# tbs4.net
KiCad netlist of a schematic drawn in EAGLE
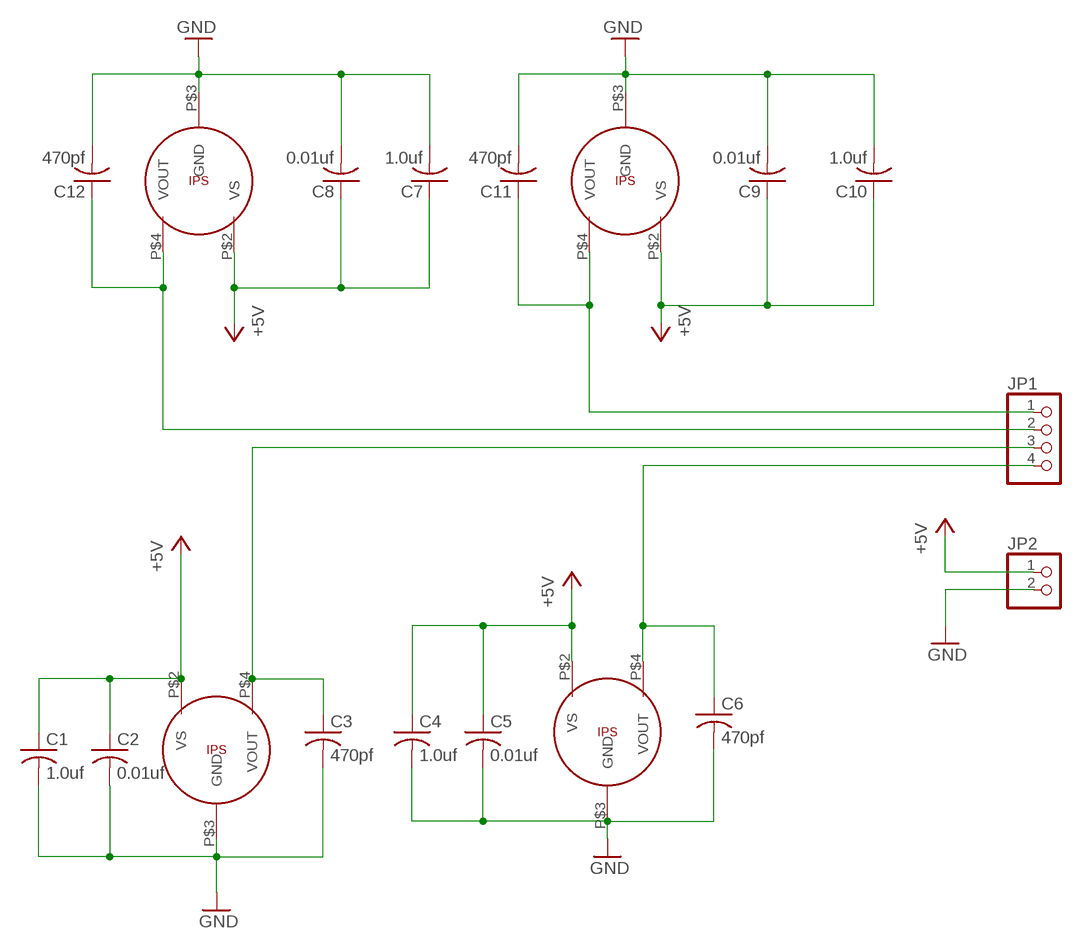
[diagram p0: schematic, sheet 1]

(export (version "E")
  (design (tool "Eeschema 10.0.6"))
  (components
    (comp (ref "C1")
      (value "1.0uf")
      (footprint "eagle-import:C0603")
      (libsource (lib "eagle-import") (part "C-USC0603"))
    )
    (comp (ref "C2")
      (value "0.01uf")
      (footprint "eagle-import:C0603")
      (libsource (lib "eagle-import") (part "C-USC0603"))
    )
    (comp (ref "C3")
      (value "470pf")
      (footprint "eagle-import:C0603")
      (libsource (lib "eagle-import") (part "C-USC0603"))
    )
    (comp (ref "C4")
      (value "1.0uf")
      (footprint "eagle-import:C0603")
      (libsource (lib "eagle-import") (part "C-USC0603"))
    )
    (comp (ref "C5")
      (value "0.01uf")
      (footprint "eagle-import:C0603")
      (libsource (lib "eagle-import") (part "C-USC0603"))
    )
    (comp (ref "C6")
      (value "470pf")
      (footprint "eagle-import:C0603")
      (libsource (lib "eagle-import") (part "C-USC0603"))
    )
    (comp (ref "C7")
      (value "1.0uf")
      (footprint "eagle-import:C0603")
      (libsource (lib "eagle-import") (part "C-USC0603"))
    )
    (comp (ref "C8")
      (value "0.01uf")
      (footprint "eagle-import:C0603")
      (libsource (lib "eagle-import") (part "C-USC0603"))
    )
    (comp (ref "C9")
      (value "0.01uf")
      (footprint "eagle-import:C0603")
      (libsource (lib "eagle-import") (part "C-USC0603"))
    )
    (comp (ref "C10")
      (value "1.0uf")
      (footprint "eagle-import:C0603")
      (libsource (lib "eagle-import") (part "C-USC0603"))
    )
    (comp (ref "C11")
      (value "470pf")
      (footprint "eagle-import:C0603")
      (libsource (lib "eagle-import") (part "C-USC0603"))
    )
    (comp (ref "C12")
      (value "470pf")
      (footprint "eagle-import:C0603")
      (libsource (lib "eagle-import") (part "C-USC0603"))
    )
    (comp (ref "IPS1")
      (value "MPXV5050VC6T1")
      (footprint "eagle-import:SOP-CASE-482A")
      (libsource (lib "eagle-import") (part "MPXV5050VC6T1"))
    )
    (comp (ref "IPS2")
      (value "MPXV5050VC6T1")
      (footprint "eagle-import:SOP-CASE-482A")
      (libsource (lib "eagle-import") (part "MPXV5050VC6T1"))
    )
    (comp (ref "IPS3")
      (value "MPXV5050VC6T1")
      (footprint "eagle-import:SOP-CASE-482A")
      (libsource (lib "eagle-import") (part "MPXV5050VC6T1"))
    )
    (comp (ref "IPS4")
      (value "MPXV5050VC6T1")
      (footprint "eagle-import:SOP-CASE-482A")
      (libsource (lib "eagle-import") (part "MPXV5050VC6T1"))
    )
    (comp (ref "JP1")
      (value "PINHD-1X4")
      (footprint "eagle-import:1X04")
      (libsource (lib "eagle-import") (part "PINHD-1X4"))
    )
    (comp (ref "JP2")
      (value "PINHD-1X2")
      (footprint "eagle-import:1X02")
      (libsource (lib "eagle-import") (part "PINHD-1X2"))
    )
  )
  (nets
    (net (code "1") (name "+5V") (class "Default")
      (node (ref "C1") (pin "1") (pinfunction "1_1") (pintype "passive"))
      (node (ref "C10") (pin "1") (pinfunction "1_1") (pintype "passive"))
      (node (ref "C2") (pin "1") (pinfunction "1_1") (pintype "passive"))
      (node (ref "C4") (pin "1") (pinfunction "1_1") (pintype "passive"))
      (node (ref "C5") (pin "1") (pinfunction "1_1") (pintype "passive"))
      (node (ref "C7") (pin "1") (pinfunction "1_1") (pintype "passive"))
      (node (ref "C8") (pin "1") (pinfunction "1_1") (pintype "passive"))
      (node (ref "C9") (pin "1") (pinfunction "1_1") (pintype "passive"))
      (node (ref "IPS1") (pin "P$2") (pinfunction "VS_P$2") (pintype "power_in"))
      (node (ref "IPS2") (pin "P$2") (pinfunction "VS_P$2") (pintype "power_in"))
      (node (ref "IPS3") (pin "P$2") (pinfunction "VS_P$2") (pintype "power_in"))
      (node (ref "IPS4") (pin "P$2") (pinfunction "VS_P$2") (pintype "power_in"))
      (node (ref "JP2") (pin "1") (pinfunction "1_1") (pintype "passive"))
    )
    (net (code "2") (name "GND") (class "Default")
      (node (ref "C1") (pin "2") (pinfunction "2_2") (pintype "passive"))
      (node (ref "C10") (pin "2") (pinfunction "2_2") (pintype "passive"))
      (node (ref "C11") (pin "2") (pinfunction "2_2") (pintype "passive"))
      (node (ref "C12") (pin "2") (pinfunction "2_2") (pintype "passive"))
      (node (ref "C2") (pin "2") (pinfunction "2_2") (pintype "passive"))
      (node (ref "C3") (pin "2") (pinfunction "2_2") (pintype "passive"))
      (node (ref "C4") (pin "2") (pinfunction "2_2") (pintype "passive"))
      (node (ref "C5") (pin "2") (pinfunction "2_2") (pintype "passive"))
      (node (ref "C6") (pin "2") (pinfunction "2_2") (pintype "passive"))
      (node (ref "C7") (pin "2") (pinfunction "2_2") (pintype "passive"))
      (node (ref "C8") (pin "2") (pinfunction "2_2") (pintype "passive"))
      (node (ref "C9") (pin "2") (pinfunction "2_2") (pintype "passive"))
      (node (ref "IPS1") (pin "P$3") (pinfunction "GND_P$3") (pintype "power_in"))
      (node (ref "IPS2") (pin "P$3") (pinfunction "GND_P$3") (pintype "power_in"))
      (node (ref "IPS3") (pin "P$3") (pinfunction "GND_P$3") (pintype "power_in"))
      (node (ref "IPS4") (pin "P$3") (pinfunction "GND_P$3") (pintype "power_in"))
      (node (ref "JP2") (pin "2") (pinfunction "2_2") (pintype "passive"))
    )
    (net (code "3") (name "Net-(IPS1-VOUT)") (class "Default")
      (node (ref "C11") (pin "1") (pinfunction "1_1") (pintype "passive"))
      (node (ref "IPS1") (pin "P$4") (pinfunction "VOUT_P$4") (pintype "output"))
      (node (ref "JP1") (pin "1") (pinfunction "1_1") (pintype "passive"))
    )
    (net (code "4") (name "Net-(IPS2-VOUT)") (class "Default")
      (node (ref "C12") (pin "1") (pinfunction "1_1") (pintype "passive"))
      (node (ref "IPS2") (pin "P$4") (pinfunction "VOUT_P$4") (pintype "output"))
      (node (ref "JP1") (pin "2") (pinfunction "2_2") (pintype "passive"))
    )
    (net (code "5") (name "Net-(IPS3-VOUT)") (class "Default")
      (node (ref "C3") (pin "1") (pinfunction "1_1") (pintype "passive"))
      (node (ref "IPS3") (pin "P$4") (pinfunction "VOUT_P$4") (pintype "output"))
      (node (ref "JP1") (pin "3") (pinfunction "3_3") (pintype "passive"))
    )
    (net (code "6") (name "Net-(IPS4-VOUT)") (class "Default")
      (node (ref "C6") (pin "1") (pinfunction "1_1") (pintype "passive"))
      (node (ref "IPS4") (pin "P$4") (pinfunction "VOUT_P$4") (pintype "output"))
      (node (ref "JP1") (pin "4") (pinfunction "4_4") (pintype "passive"))
    )
  )
)
